# touringmach1.net
KiCad netlist of a schematic drawn in EAGLE
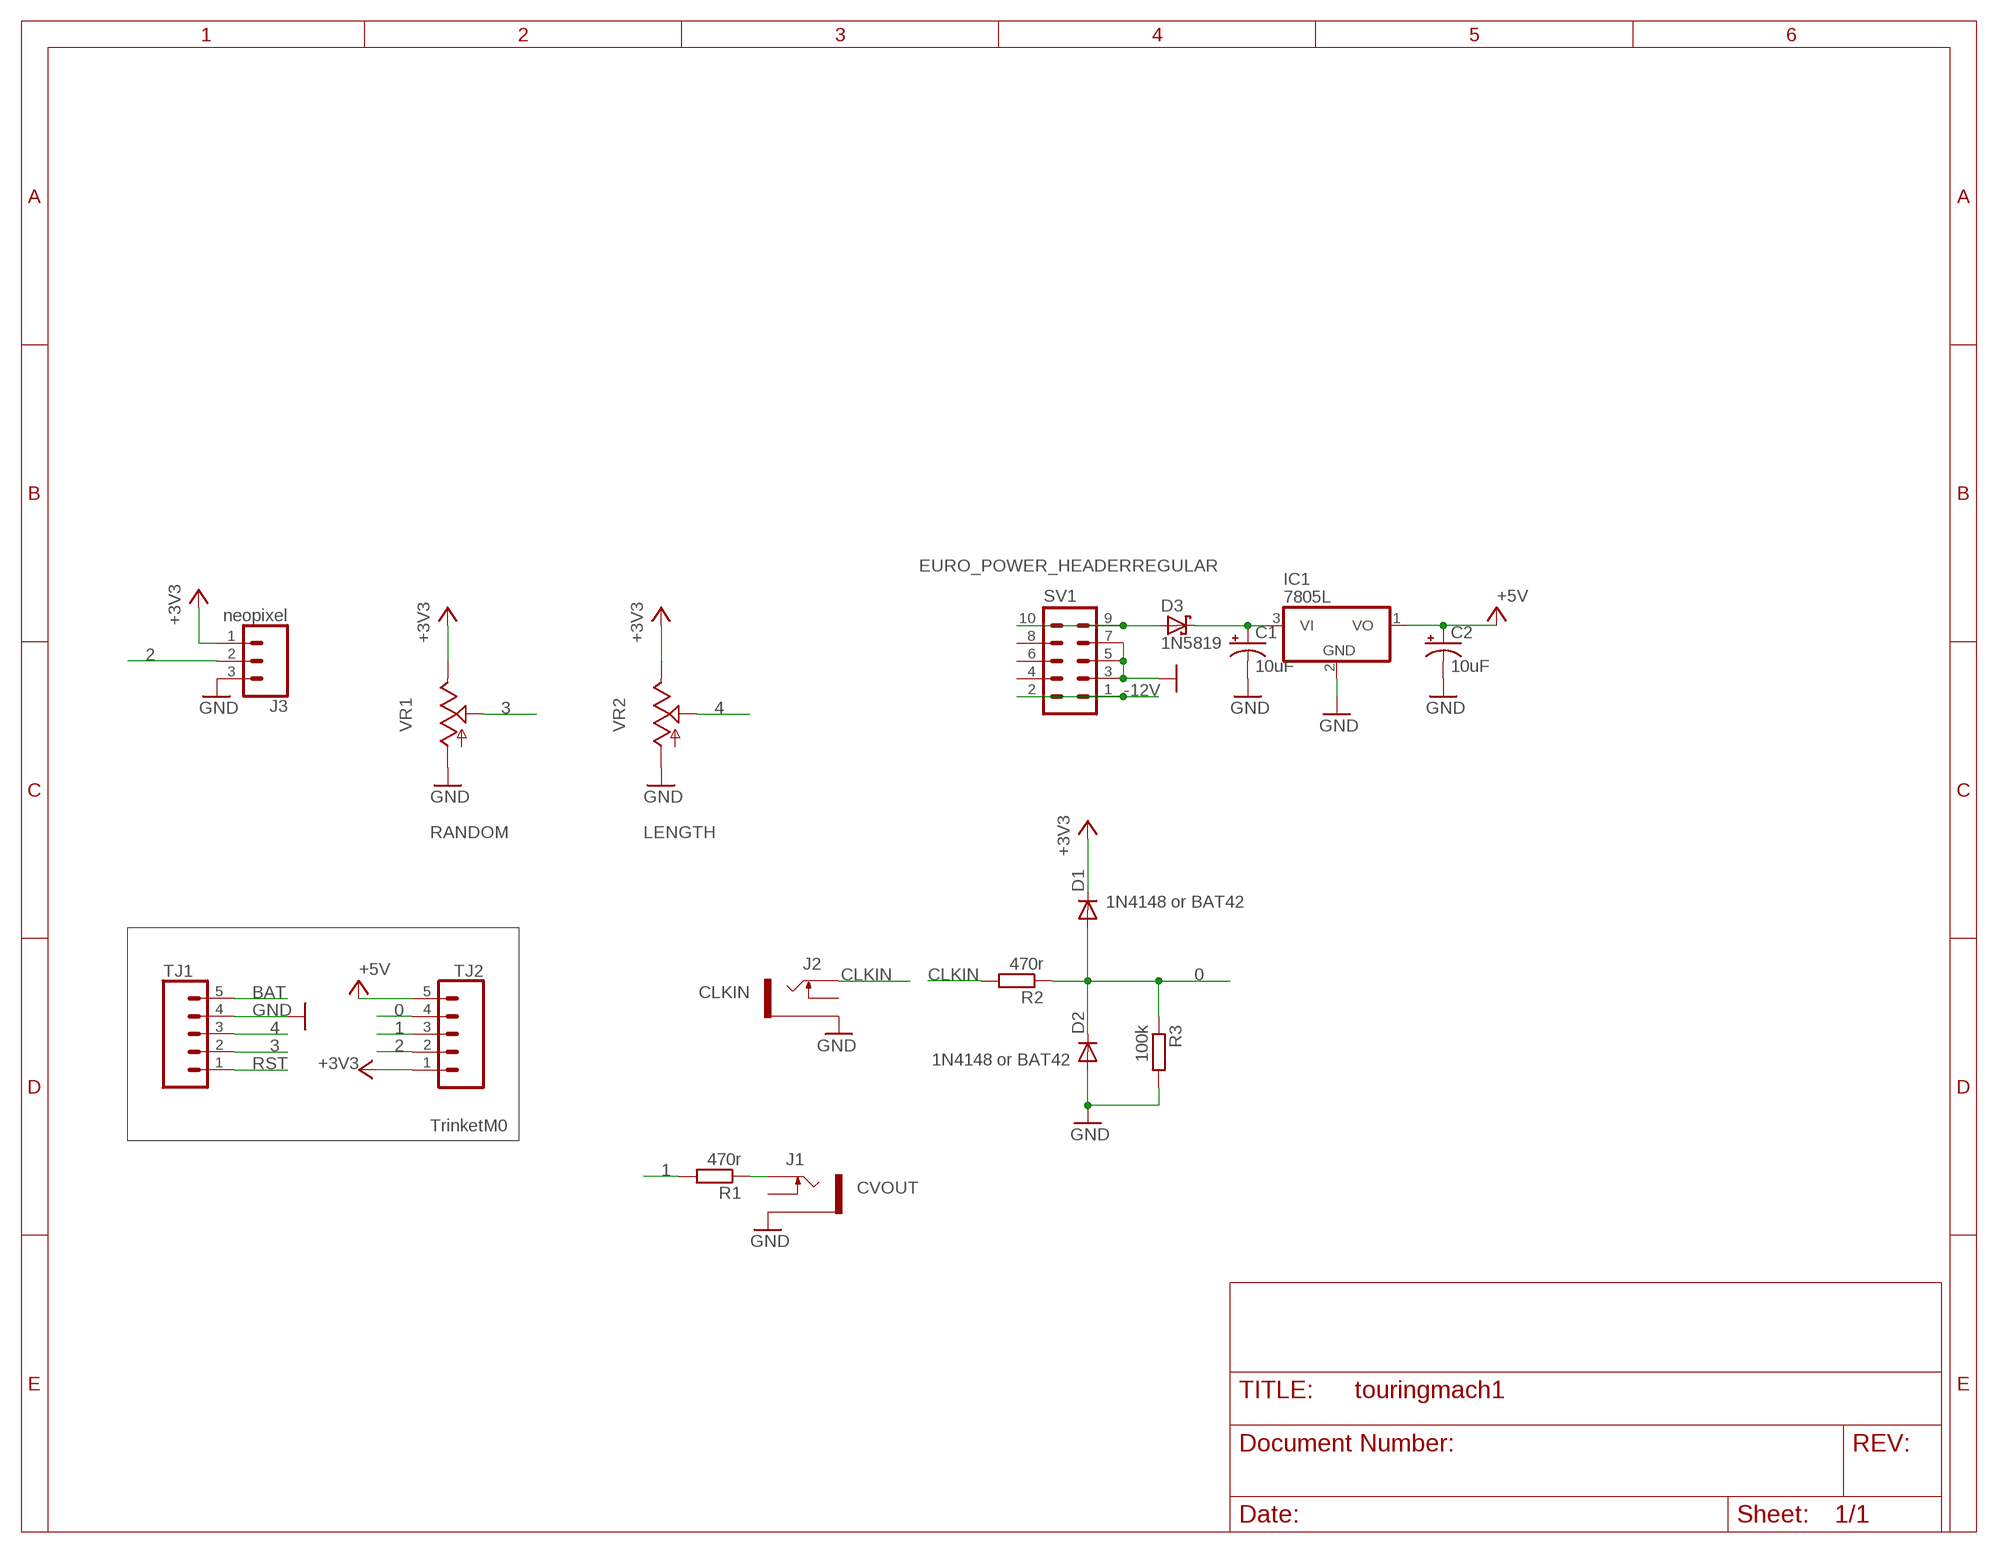
[diagram p0: schematic, sheet 1]

(export (version "E")
  (design (tool "Eeschema 10.0.6"))
  (components
    (comp (ref "C1")
      (value "10uF")
      (footprint "eagle-import:E2,5-6")
      (libsource (lib "eagle-import") (part "CPOL-USE2.5-6"))
    )
    (comp (ref "C2")
      (value "10uF")
      (footprint "eagle-import:E2,5-6")
      (libsource (lib "eagle-import") (part "CPOL-USE2.5-6"))
    )
    (comp (ref "D1")
      (value "1N4148 or BAT42")
      (footprint "eagle-import:DO34-7")
      (libsource (lib "eagle-import") (part "BAT42"))
    )
    (comp (ref "D2")
      (value "1N4148 or BAT42")
      (footprint "eagle-import:DO34-7")
      (libsource (lib "eagle-import") (part "BAT42"))
    )
    (comp (ref "D3")
      (value "1N5819")
      (footprint "eagle-import:DO41-7.6")
      (libsource (lib "eagle-import") (part "1N5819-B"))
    )
    (comp (ref "IC1")
      (value "7805L")
      (footprint "eagle-import:TO92")
      (libsource (lib "eagle-import") (part "78L05"))
    )
    (comp (ref "J1")
      (value "THONKICONNOLD")
      (footprint "eagle-import:THONKICONN")
      (libsource (lib "eagle-import") (part "THONKICONNOLD"))
    )
    (comp (ref "J2")
      (value "THONKICONNOLD")
      (footprint "eagle-import:THONKICONN")
      (libsource (lib "eagle-import") (part "THONKICONNOLD"))
    )
    (comp (ref "J3")
      (value "neopixel")
      (footprint "eagle-import:1X03")
      (libsource (lib "eagle-import") (part "CONN_03"))
    )
    (comp (ref "R1")
      (value "470r")
      (footprint "eagle-import:7MM_RESISTOR")
      (libsource (lib "eagle-import") (part "RESISTOR7MM"))
    )
    (comp (ref "R2")
      (value "470r")
      (footprint "eagle-import:7MM_RESISTOR")
      (libsource (lib "eagle-import") (part "RESISTOR7MM"))
    )
    (comp (ref "R3")
      (value "100k")
      (footprint "eagle-import:7MM_RESISTOR")
      (libsource (lib "eagle-import") (part "RESISTOR7MM"))
    )
    (comp (ref "SV1")
      (value "EURO_POWER_HEADERREGULAR")
      (footprint "eagle-import:EURO_POWER_HEADER")
      (libsource (lib "eagle-import") (part "EURO_POWER_HEADERREGULAR"))
    )
    (comp (ref "TJ1")
      (value "CONN_05")
      (footprint "eagle-import:1X05")
      (libsource (lib "eagle-import") (part "CONN_05"))
    )
    (comp (ref "TJ2")
      (value "CONN_05")
      (footprint "eagle-import:1X05")
      (libsource (lib "eagle-import") (part "CONN_05"))
    )
    (comp (ref "VR1")
      (value "9MM_SNAP-IN_POT_")
      (footprint "eagle-import:9MM_SNAP-IN_POT")
      (libsource (lib "eagle-import") (part "9MM_SNAP-IN_POT_"))
    )
    (comp (ref "VR2")
      (value "9MM_SNAP-IN_POT_")
      (footprint "eagle-import:9MM_SNAP-IN_POT")
      (libsource (lib "eagle-import") (part "9MM_SNAP-IN_POT_"))
    )
  )
  (nets
    (net (code "1") (name "+3V3") (class "Default")
      (node (ref "D1") (pin "C") (pinfunction "C_C") (pintype "passive"))
      (node (ref "J3") (pin "1") (pinfunction "1_1") (pintype "passive"))
      (node (ref "TJ2") (pin "1") (pinfunction "1_1") (pintype "passive"))
      (node (ref "VR1") (pin "3") (pinfunction "E_3") (pintype "passive"))
      (node (ref "VR2") (pin "3") (pinfunction "E_3") (pintype "passive"))
    )
    (net (code "2") (name "+5V") (class "Default")
      (node (ref "C2") (pin "+") (pinfunction "+_+") (pintype "passive"))
      (node (ref "IC1") (pin "1") (pinfunction "VO_1") (pintype "passive"))
      (node (ref "TJ2") (pin "5") (pinfunction "5_5") (pintype "passive"))
    )
    (net (code "3") (name "/-12V") (class "Default")
      (node (ref "SV1") (pin "1") (pinfunction "1_1") (pintype "passive"))
      (node (ref "SV1") (pin "2") (pinfunction "2_2") (pintype "passive"))
    )
    (net (code "4") (name "/0") (class "Default")
      (node (ref "D1") (pin "A") (pinfunction "A_A") (pintype "passive"))
      (node (ref "D2") (pin "C") (pinfunction "C_C") (pintype "passive"))
      (node (ref "R2") (pin "1") (pinfunction "1_1") (pintype "passive"))
      (node (ref "R3") (pin "1") (pinfunction "1_1") (pintype "passive"))
      (node (ref "TJ2") (pin "4") (pinfunction "4_4") (pintype "passive"))
    )
    (net (code "5") (name "/1") (class "Default")
      (node (ref "R1") (pin "2") (pinfunction "2_2") (pintype "passive"))
      (node (ref "TJ2") (pin "3") (pinfunction "3_3") (pintype "passive"))
    )
    (net (code "6") (name "/2") (class "Default")
      (node (ref "J3") (pin "2") (pinfunction "2_2") (pintype "passive"))
      (node (ref "TJ2") (pin "2") (pinfunction "2_2") (pintype "passive"))
    )
    (net (code "7") (name "/3") (class "Default")
      (node (ref "TJ1") (pin "2") (pinfunction "2_2") (pintype "passive"))
      (node (ref "VR1") (pin "2") (pinfunction "S_2") (pintype "passive"))
    )
    (net (code "8") (name "/4") (class "Default")
      (node (ref "TJ1") (pin "3") (pinfunction "3_3") (pintype "passive"))
      (node (ref "VR2") (pin "2") (pinfunction "S_2") (pintype "passive"))
    )
    (net (code "9") (name "/BAT") (class "Default")
      (node (ref "TJ1") (pin "5") (pinfunction "5_5") (pintype "passive"))
    )
    (net (code "10") (name "/CLKIN") (class "Default")
      (node (ref "J2") (pin "P$3_TIP") (pinfunction "TIP_P$3_TIP") (pintype "passive"))
      (node (ref "R2") (pin "2") (pinfunction "2_2") (pintype "passive"))
    )
    (net (code "11") (name "/RST") (class "Default")
      (node (ref "TJ1") (pin "1") (pinfunction "1_1") (pintype "passive"))
    )
    (net (code "12") (name "GND") (class "Default")
      (node (ref "C1") (pin "-") (pinfunction "-_-") (pintype "passive"))
      (node (ref "C2") (pin "-") (pinfunction "-_-") (pintype "passive"))
      (node (ref "D2") (pin "A") (pinfunction "A_A") (pintype "passive"))
      (node (ref "IC1") (pin "2") (pinfunction "GND_2") (pintype "passive"))
      (node (ref "J1") (pin "P$1_SLEEVE") (pinfunction "SLEEVE_P$1_SLEEVE") (pintype "passive"))
      (node (ref "J2") (pin "P$1_SLEEVE") (pinfunction "SLEEVE_P$1_SLEEVE") (pintype "passive"))
      (node (ref "J3") (pin "3") (pinfunction "3_3") (pintype "passive"))
      (node (ref "R3") (pin "2") (pinfunction "2_2") (pintype "passive"))
      (node (ref "SV1") (pin "3") (pinfunction "3_3") (pintype "passive"))
      (node (ref "SV1") (pin "5") (pinfunction "5_5") (pintype "passive"))
      (node (ref "SV1") (pin "7") (pinfunction "7_7") (pintype "passive"))
      (node (ref "TJ1") (pin "4") (pinfunction "4_4") (pintype "passive"))
      (node (ref "VR1") (pin "1") (pinfunction "A_1") (pintype "passive"))
      (node (ref "VR2") (pin "1") (pinfunction "A_1") (pintype "passive"))
    )
    (net (code "13") (name "Net-(D3-PadA)") (class "Default")
      (node (ref "D3") (pin "A") (pinfunction "A_A") (pintype "passive"))
      (node (ref "SV1") (pin "10") (pinfunction "10_10") (pintype "passive"))
      (node (ref "SV1") (pin "9") (pinfunction "9_9") (pintype "passive"))
    )
    (net (code "14") (name "Net-(IC1-VI)") (class "Default")
      (node (ref "C1") (pin "+") (pinfunction "+_+") (pintype "passive"))
      (node (ref "D3") (pin "C") (pinfunction "C_C") (pintype "passive"))
      (node (ref "IC1") (pin "3") (pinfunction "VI_3") (pintype "input"))
    )
    (net (code "15") (name "Net-(J1-TIP)") (class "Default")
      (node (ref "J1") (pin "P$3_TIP") (pinfunction "TIP_P$3_TIP") (pintype "passive"))
      (node (ref "R1") (pin "1") (pinfunction "1_1") (pintype "passive"))
    )
    (net (code "16") (name "unconnected-(J1-SWITCH-PadP$2_SWITCH)") (class "Default")
      (node (ref "J1") (pin "P$2_SWITCH") (pinfunction "SWITCH_P$2_SWITCH") (pintype "passive"))
    )
    (net (code "17") (name "unconnected-(J2-SWITCH-PadP$2_SWITCH)") (class "Default")
      (node (ref "J2") (pin "P$2_SWITCH") (pinfunction "SWITCH_P$2_SWITCH") (pintype "passive"))
    )
    (net (code "18") (name "unconnected-(SV1-Pad4)") (class "Default")
      (node (ref "SV1") (pin "4") (pinfunction "4_4") (pintype "passive"))
    )
    (net (code "19") (name "unconnected-(SV1-Pad6)") (class "Default")
      (node (ref "SV1") (pin "6") (pinfunction "6_6") (pintype "passive"))
    )
    (net (code "20") (name "unconnected-(SV1-Pad8)") (class "Default")
      (node (ref "SV1") (pin "8") (pinfunction "8_8") (pintype "passive"))
    )
  )
)
